# LPEDT_revA1_bikeit_DISPLAY.net
KiCad netlist of a schematic drawn in Altium Designer
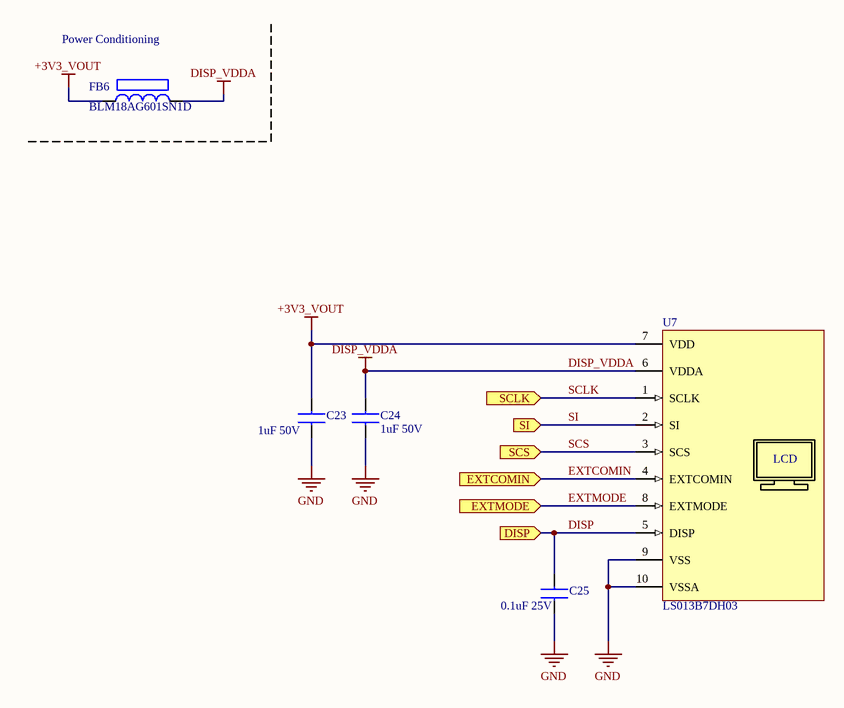
[diagram p0: LPEDT_revA1_bikeit_DISPLAY.SchDoc]

(export (version "E")
  (design (tool "Eeschema 10.0.6"))
  (components
    (comp (ref "C23")
      (value "1uF 50V")
      (footprint "CAP_0603_1.60mm*0.80mm")
      (description "CAP, MLCC, AEC-Q200, X5R, 1uF, 50V, 0603")
      (fields
        (field (name "MANUFACTURER") "Murata")
        (field (name "MANUFACTURER PART NUMBER") "GRT188R61H105KE13D")
      )
      (libsource (lib "LPEDT_revA1_bikeit_IL") (part "GRT188R61H105KE13D"))
    )
    (comp (ref "C24")
      (value "1uF 50V")
      (footprint "CAP_0603_1.60mm*0.80mm")
      (description "CAP, MLCC, AEC-Q200, X5R, 1uF, 50V, 0603")
      (fields
        (field (name "MANUFACTURER") "Murata")
        (field (name "MANUFACTURER PART NUMBER") "GRT188R61H105KE13D")
      )
      (libsource (lib "LPEDT_revA1_bikeit_IL") (part "GRT188R61H105KE13D"))
    )
    (comp (ref "C25")
      (value "0.1uF 25V")
      (footprint "CAP_0603_1.60mm*0.80mm")
      (description "CAP CER 0.1UF 25V X7R 0603")
      (fields
        (field (name "MANUFACTURER") "Murata")
        (field (name "MANUFACTURER PART NUMBER") "GCJ188R71E104KA12D")
      )
      (libsource (lib "LPEDT_revA1_bikeit_IL") (part "GCJ188R71E104KA12D"))
    )
    (comp (ref "FB6")
      (value "BLM18AG601SN1D")
      (footprint "Chip2PinSM127P600-8N")
      (description "Ferrite Bead, 0603 / 1608, 600 ohm, 500 mA, Série BLM18A, 0.38 ohm, ± 25%")
      (fields (field (name "MANUFACTURER") "Murata") (field (name "TOLERANCE") "25%"))
      (libsource (lib "LPEDT_revA1_bikeit_IL") (part "BLM18AG601SN1D"))
    )
    (comp (ref "U7")
      (value "LS013B7DH03")
      (description "1.28 Memory LCD 128x128 Tranf HR-TFT")
      (fields (field (name "MANUFACTURER") "Sharp"))
      (libsource (lib "LPEDT_revA1_bikeit") (part "LS013B7DH03"))
    )
  )
  (nets
    (net (code "1") (name "+3V3_VOUT") (class "Default")
      (node (ref "C23") (pin "1") (pinfunction "1_1") (pintype "passive"))
      (node (ref "FB6") (pin "1") (pinfunction "1_1") (pintype "passive"))
      (node (ref "U7") (pin "7") (pinfunction "VDD_7") (pintype "power_in"))
    )
    (net (code "2") (name "/DISP") (class "Default")
      (node (ref "C25") (pin "1") (pinfunction "1_1") (pintype "passive"))
      (node (ref "U7") (pin "5") (pinfunction "DISP_5") (pintype "input"))
    )
    (net (code "3") (name "/EXTCOMIN") (class "Default")
      (node (ref "U7") (pin "4") (pinfunction "EXTCOMIN_4") (pintype "input"))
    )
    (net (code "4") (name "/EXTMODE") (class "Default")
      (node (ref "U7") (pin "8") (pinfunction "EXTMODE_8") (pintype "input"))
    )
    (net (code "5") (name "/SCLK") (class "Default")
      (node (ref "U7") (pin "1") (pinfunction "SCLK_1") (pintype "input"))
    )
    (net (code "6") (name "/SCS") (class "Default")
      (node (ref "U7") (pin "3") (pinfunction "SCS_3") (pintype "input"))
    )
    (net (code "7") (name "/SI") (class "Default")
      (node (ref "U7") (pin "2") (pinfunction "SI_2") (pintype "input"))
    )
    (net (code "8") (name "DISP_VDDA") (class "Default")
      (node (ref "C24") (pin "1") (pinfunction "1_1") (pintype "passive"))
      (node (ref "FB6") (pin "2") (pinfunction "2_2") (pintype "passive"))
      (node (ref "U7") (pin "6") (pinfunction "VDDA_6") (pintype "power_in"))
    )
    (net (code "9") (name "GND") (class "Default")
      (node (ref "C23") (pin "2") (pinfunction "2_2") (pintype "passive"))
      (node (ref "C24") (pin "2") (pinfunction "2_2") (pintype "passive"))
      (node (ref "C25") (pin "2") (pinfunction "2_2") (pintype "passive"))
      (node (ref "U7") (pin "10") (pinfunction "VSSA_10") (pintype "passive"))
      (node (ref "U7") (pin "9") (pinfunction "VSS_9") (pintype "passive"))
    )
  )
)
